# FTDI.net
KiCad netlist of a schematic drawn in Altium Designer
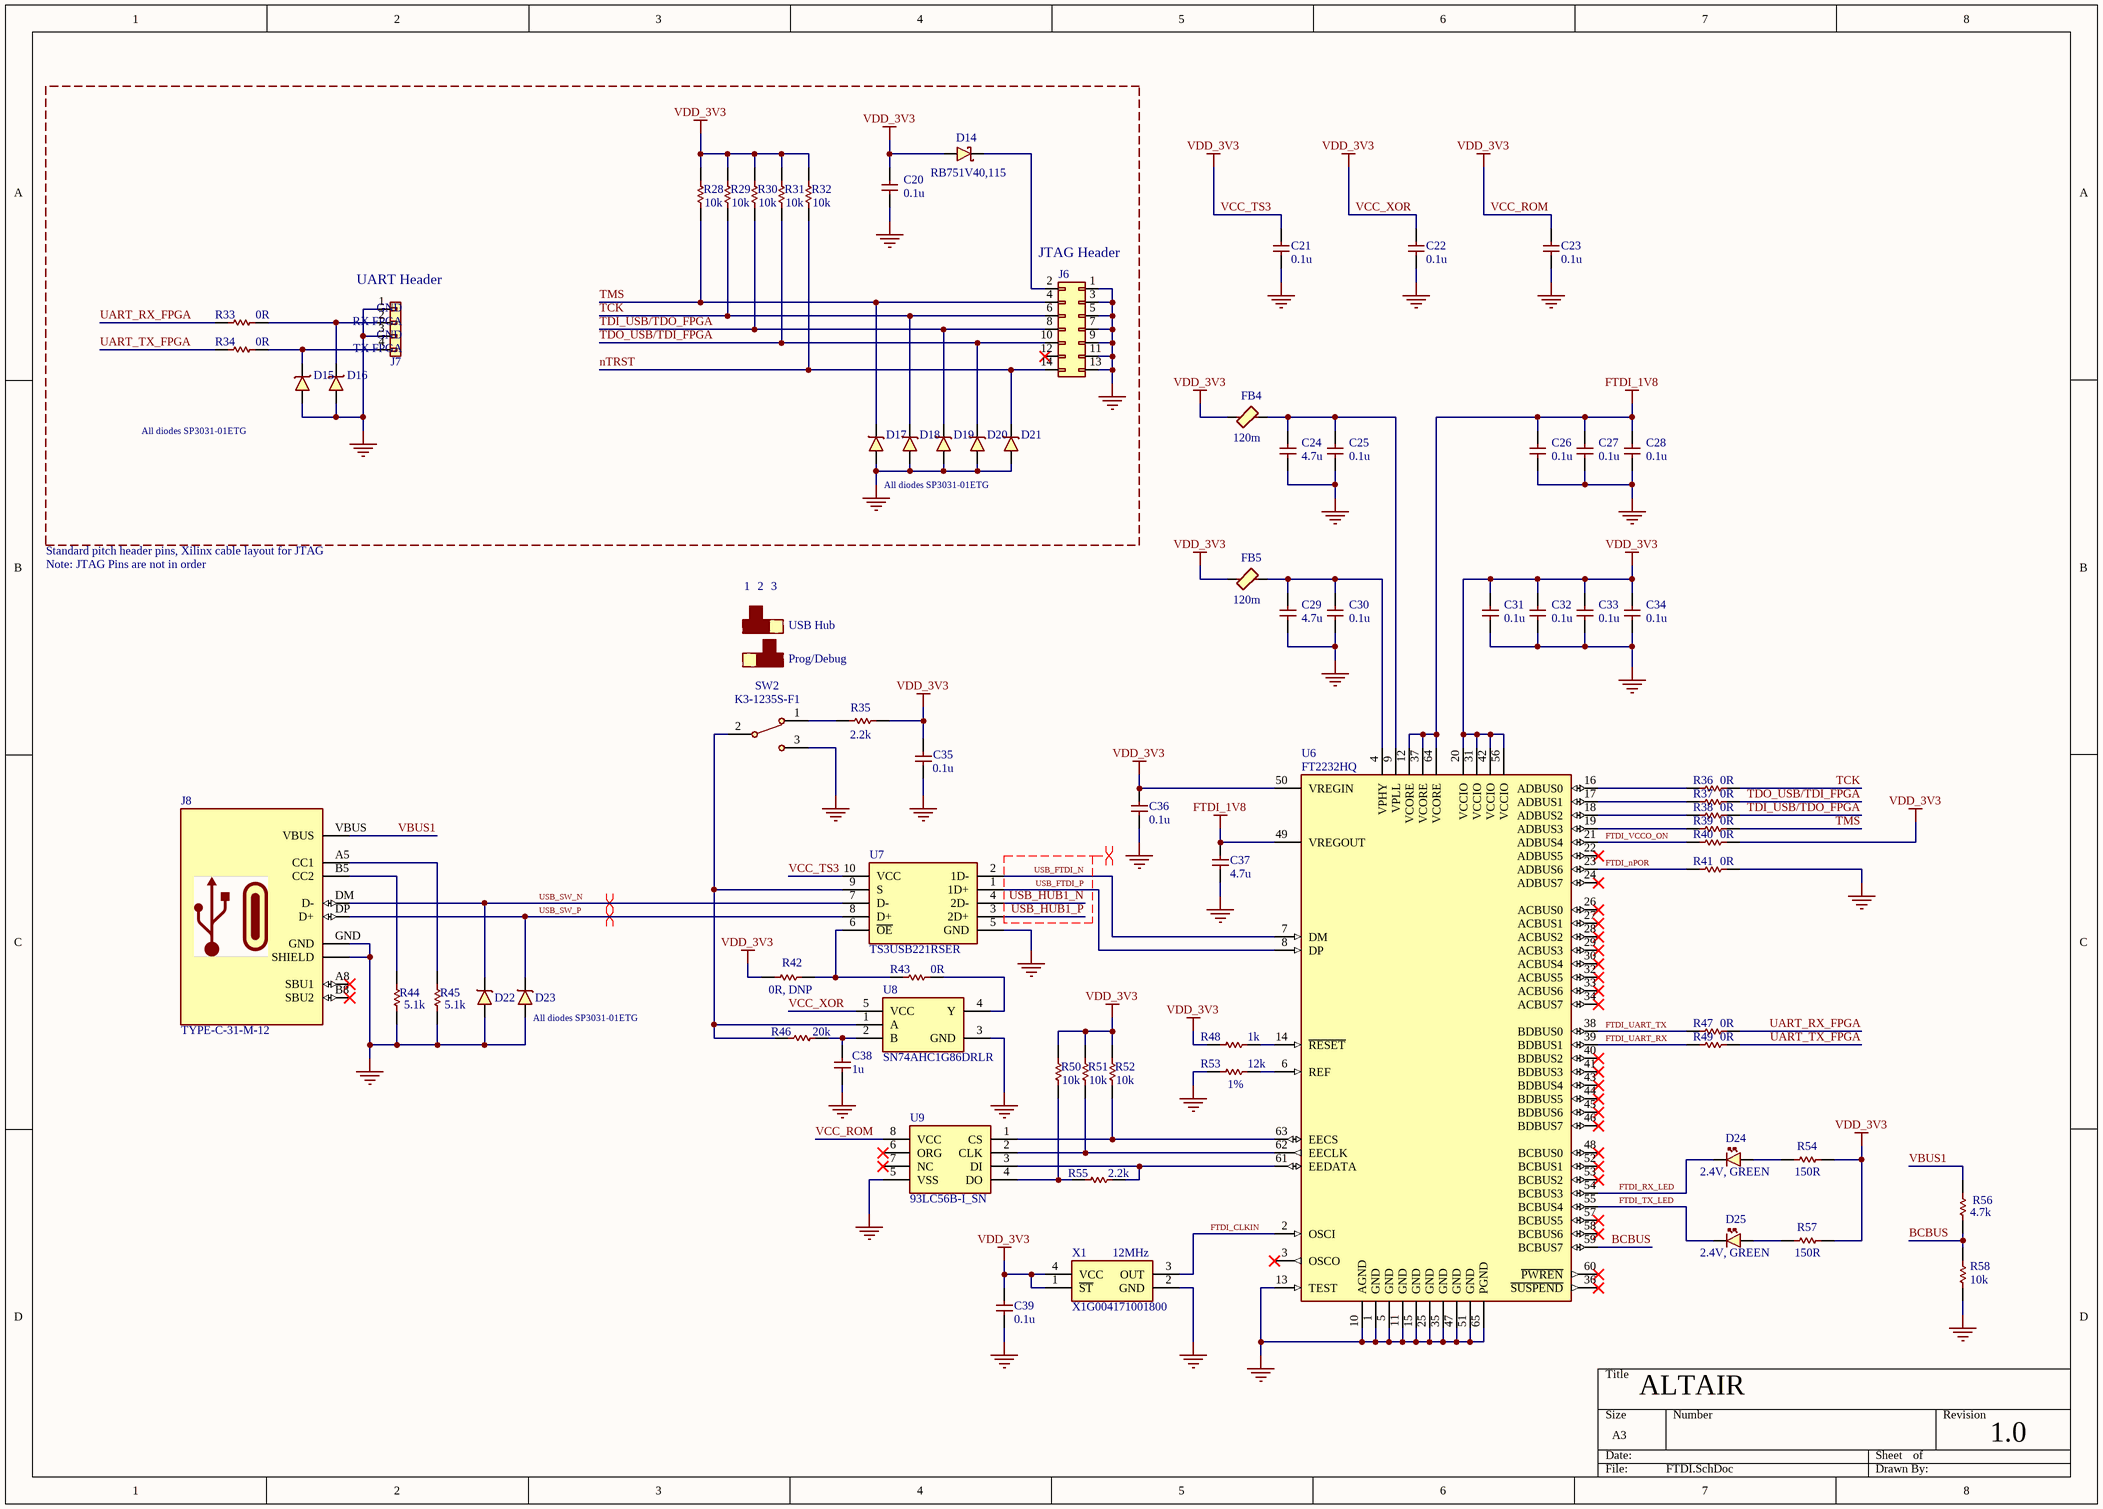
[diagram p0: FTDI.SchDoc]

(export (version "E")
  (design (tool "Eeschema 10.0.6"))
  (components
    (comp (ref "C20")
      (value "0.1u")
      (footprint "CAP_0402")
      (description "Capacitor SMD 0402")
      (fields (field (name "PART NO") "CL05B104KO5NNNC") (field (name "JLCPCB PART #") "C338112"))
      (libsource (lib "personalGenericLib") (part "CAP_0402"))
    )
    (comp (ref "C21")
      (value "0.1u")
      (footprint "CAP_0402")
      (description "Capacitor SMD 0402")
      (fields (field (name "PART NO") "CL05B104KO5NNNC") (field (name "JLCPCB PART #") "C338112"))
      (libsource (lib "personalGenericLib") (part "CAP_0402"))
    )
    (comp (ref "C22")
      (value "0.1u")
      (footprint "CAP_0402")
      (description "Capacitor SMD 0402")
      (fields (field (name "PART NO") "CL05B104KO5NNNC") (field (name "JLCPCB PART #") "C338112"))
      (libsource (lib "personalGenericLib") (part "CAP_0402"))
    )
    (comp (ref "C23")
      (value "0.1u")
      (footprint "CAP_0402")
      (description "Capacitor SMD 0402")
      (fields (field (name "PART NO") "CL05B104KO5NNNC") (field (name "JLCPCB PART #") "C338112"))
      (libsource (lib "personalGenericLib") (part "CAP_0402"))
    )
    (comp (ref "C24")
      (value "4.7u")
      (footprint "CAP_0402")
      (description "Capacitor SMD 0402")
      (fields (field (name "PART NO") "HGC0402R5475M250NTEJ") (field (name "JLCPCB PART #") "C22367824"))
      (libsource (lib "personalGenericLib") (part "CAP_0402"))
    )
    (comp (ref "C25")
      (value "0.1u")
      (footprint "CAP_0402")
      (description "Capacitor SMD 0402")
      (fields (field (name "PART NO") "CL05B104KO5NNNC") (field (name "JLCPCB PART #") "C338112"))
      (libsource (lib "personalGenericLib") (part "CAP_0402"))
    )
    (comp (ref "C26")
      (value "0.1u")
      (footprint "CAP_0402")
      (description "Capacitor SMD 0402")
      (fields (field (name "PART NO") "CL05B104KO5NNNC") (field (name "JLCPCB PART #") "C338112"))
      (libsource (lib "personalGenericLib") (part "CAP_0402"))
    )
    (comp (ref "C27")
      (value "0.1u")
      (footprint "CAP_0402")
      (description "Capacitor SMD 0402")
      (fields (field (name "PART NO") "CL05B104KO5NNNC") (field (name "JLCPCB PART #") "C338112"))
      (libsource (lib "personalGenericLib") (part "CAP_0402"))
    )
    (comp (ref "C28")
      (value "0.1u")
      (footprint "CAP_0402")
      (description "Capacitor SMD 0402")
      (fields (field (name "PART NO") "CL05B104KO5NNNC") (field (name "JLCPCB PART #") "C338112"))
      (libsource (lib "personalGenericLib") (part "CAP_0402"))
    )
    (comp (ref "C29")
      (value "4.7u")
      (footprint "CAP_0402")
      (description "Capacitor SMD 0402")
      (fields (field (name "PART NO") "HGC0402R5475M250NTEJ") (field (name "JLCPCB PART #") "C22367824"))
      (libsource (lib "personalGenericLib") (part "CAP_0402"))
    )
    (comp (ref "C30")
      (value "0.1u")
      (footprint "CAP_0402")
      (description "Capacitor SMD 0402")
      (fields (field (name "PART NO") "CL05B104KO5NNNC") (field (name "JLCPCB PART #") "C338112"))
      (libsource (lib "personalGenericLib") (part "CAP_0402"))
    )
    (comp (ref "C31")
      (value "0.1u")
      (footprint "CAP_0402")
      (description "Capacitor SMD 0402")
      (fields (field (name "PART NO") "CL05B104KO5NNNC") (field (name "JLCPCB PART #") "C338112"))
      (libsource (lib "personalGenericLib") (part "CAP_0402"))
    )
    (comp (ref "C32")
      (value "0.1u")
      (footprint "CAP_0402")
      (description "Capacitor SMD 0402")
      (fields (field (name "PART NO") "CL05B104KO5NNNC") (field (name "JLCPCB PART #") "C338112"))
      (libsource (lib "personalGenericLib") (part "CAP_0402"))
    )
    (comp (ref "C33")
      (value "0.1u")
      (footprint "CAP_0402")
      (description "Capacitor SMD 0402")
      (fields (field (name "PART NO") "CL05B104KO5NNNC") (field (name "JLCPCB PART #") "C338112"))
      (libsource (lib "personalGenericLib") (part "CAP_0402"))
    )
    (comp (ref "C34")
      (value "0.1u")
      (footprint "CAP_0402")
      (description "Capacitor SMD 0402")
      (fields (field (name "PART NO") "CL05B104KO5NNNC") (field (name "JLCPCB PART #") "C338112"))
      (libsource (lib "personalGenericLib") (part "CAP_0402"))
    )
    (comp (ref "C35")
      (value "0.1u")
      (footprint "CAP_0402")
      (description "Capacitor SMD 0402")
      (fields (field (name "PART NO") "CL05B104KO5NNNC") (field (name "JLCPCB PART #") "C338112"))
      (libsource (lib "personalGenericLib") (part "CAP_0402"))
    )
    (comp (ref "C36")
      (value "0.1u")
      (footprint "CAP_0402")
      (description "Capacitor SMD 0402")
      (fields (field (name "PART NO") "CL05B104KO5NNNC") (field (name "JLCPCB PART #") "C338112"))
      (libsource (lib "personalGenericLib") (part "CAP_0402"))
    )
    (comp (ref "C37")
      (value "4.7u")
      (footprint "CAP_0402")
      (description "Capacitor SMD 0402")
      (fields (field (name "PART NO") "HGC0402R5475M250NTEJ") (field (name "JLCPCB PART #") "C22367824"))
      (libsource (lib "personalGenericLib") (part "CAP_0402"))
    )
    (comp (ref "C38")
      (value "1u")
      (footprint "CAP_0402")
      (description "Capacitor SMD 0402")
      (fields (field (name "JLCPCB PART #") "C14445") (field (name "PART NO") "CL05A105KP5NNNC"))
      (libsource (lib "personalGenericLib") (part "CAP_0402"))
    )
    (comp (ref "C39")
      (value "0.1u")
      (footprint "CAP_0402")
      (description "Capacitor SMD 0402")
      (fields (field (name "PART NO") "CL05B104KO5NNNC") (field (name "JLCPCB PART #") "C338112"))
      (libsource (lib "personalGenericLib") (part "CAP_0402"))
    )
    (comp (ref "D14")
      (value "RB751V40,115")
      (footprint "SOD2512X110N")
      (description "Schottky Diode")
      (fields (field (name "JLCPCB PART #") "C553814"))
      (libsource (lib "personalGenericLib") (part "RB751V40,115"))
    )
    (comp (ref "D15")
      (value "SP3031-01ETG")
      (footprint "SP303101ETG")
      (description "TVS Diode (Uni-directional)")
      (fields (field (name "JLCPCB PART #") "C207283"))
      (libsource (lib "personalGenericLib") (part "SP3031-01ETG"))
    )
    (comp (ref "D16")
      (value "SP3031-01ETG")
      (footprint "SP303101ETG")
      (description "TVS Diode (Uni-directional)")
      (fields (field (name "JLCPCB PART #") "C207283"))
      (libsource (lib "personalGenericLib") (part "SP3031-01ETG"))
    )
    (comp (ref "D17")
      (value "SP3031-01ETG")
      (footprint "SP303101ETG")
      (description "TVS Diode (Uni-directional)")
      (fields (field (name "JLCPCB PART #") "C207283"))
      (libsource (lib "personalGenericLib") (part "SP3031-01ETG"))
    )
    (comp (ref "D18")
      (value "SP3031-01ETG")
      (footprint "SP303101ETG")
      (description "TVS Diode (Uni-directional)")
      (fields (field (name "JLCPCB PART #") "C207283"))
      (libsource (lib "personalGenericLib") (part "SP3031-01ETG"))
    )
    (comp (ref "D19")
      (value "SP3031-01ETG")
      (footprint "SP303101ETG")
      (description "TVS Diode (Uni-directional)")
      (fields (field (name "JLCPCB PART #") "C207283"))
      (libsource (lib "personalGenericLib") (part "SP3031-01ETG"))
    )
    (comp (ref "D20")
      (value "SP3031-01ETG")
      (footprint "SP303101ETG")
      (description "TVS Diode (Uni-directional)")
      (fields (field (name "JLCPCB PART #") "C207283"))
      (libsource (lib "personalGenericLib") (part "SP3031-01ETG"))
    )
    (comp (ref "D21")
      (value "SP3031-01ETG")
      (footprint "SP303101ETG")
      (description "TVS Diode (Uni-directional)")
      (fields (field (name "JLCPCB PART #") "C207283"))
      (libsource (lib "personalGenericLib") (part "SP3031-01ETG"))
    )
    (comp (ref "D22")
      (value "SP3031-01ETG")
      (footprint "SP303101ETG")
      (description "TVS Diode (Uni-directional)")
      (fields (field (name "JLCPCB PART #") "C207283"))
      (libsource (lib "personalGenericLib") (part "SP3031-01ETG"))
    )
    (comp (ref "D23")
      (value "SP3031-01ETG")
      (footprint "SP303101ETG")
      (description "TVS Diode (Uni-directional)")
      (fields (field (name "JLCPCB PART #") "C207283"))
      (libsource (lib "personalGenericLib") (part "SP3031-01ETG"))
    )
    (comp (ref "D24")
      (value "GREEN")
      (footprint "LED_0805_GREEN")
      (description "LED 0805 GREEN SMD")
      (fields
        (field (name "JLCPCB PART #") "C2986046")
        (field (name "NOTE/MISC") "2.4V, GREEN")
        (field (name "PART NO") "17-21SYGC/S530-E2/TR8")
      )
      (libsource (lib "personalGenericLib") (part "LED_0805_GREEN"))
    )
    (comp (ref "D25")
      (value "GREEN")
      (footprint "LED_0805_GREEN")
      (description "LED 0805 GREEN SMD")
      (fields
        (field (name "JLCPCB PART #") "C2986046")
        (field (name "NOTE/MISC") "2.4V, GREEN")
        (field (name "PART NO") "17-21SYGC/S530-E2/TR8")
      )
      (libsource (lib "personalGenericLib") (part "LED_0805_GREEN"))
    )
    (comp (ref "FB4")
      (value "120m")
      (footprint "FB_0201")
      (description "Ferrite Bead SMD 0201")
      (fields (field (name "PART NO") "MPZ0603S121HT000") (field (name "JLCPCB PART #") "C695597"))
      (libsource (lib "personalGenericLib") (part "FB_0201"))
    )
    (comp (ref "FB5")
      (value "120m")
      (footprint "FB_0201")
      (description "Ferrite Bead SMD 0201")
      (fields (field (name "PART NO") "MPZ0603S121HT000") (field (name "JLCPCB PART #") "C695597"))
      (libsource (lib "personalGenericLib") (part "FB_0201"))
    )
    (comp (ref "J6")
      (value "2x7Header")
      (footprint "67996114HLF")
      (description "Standard 2x7 pin 2.54mm pitch connector")
      (fields (field (name "JLCPCB PART #") "C706897") (field (name "PART NO") "X6521WV-2x07H-C60D30"))
      (libsource (lib "personalGenericLib") (part "2x7Header"))
    )
    (comp (ref "J7")
      (value "4xHeader")
      (footprint "HDRV4W95P0X254_1X4_1016X254X854P")
      (description "Standard 4 pin 2.54mm pitch connector")
      (fields (field (name "JLCPCB PART #") "C706876") (field (name "PART NO") "X6511WV-04H-C60D30"))
      (libsource (lib "personalGenericLib") (part "4xHeader"))
    )
    (comp (ref "J8")
      (value "TYPE-C-31-M-12")
      (footprint "HRO_TYPE-C-31-M-12")
      (description "USB2.0, Type C, Top mount, CH 1.68mm, Dual Row SMT")
      (fields (field (name "JLCPCB PART #") "C165948"))
      (libsource (lib "personalGenericLib") (part "TYPE-C-31-M-12"))
    )
    (comp (ref "R28")
      (value "10k")
      (footprint "RES_0402")
      (description "Resistor SMD 0402")
      (fields (field (name "JLCPCB PART #") "C60489") (field (name "PART NO") "RC0402JR-0710KL"))
      (libsource (lib "personalGenericLib") (part "RES_0402"))
    )
    (comp (ref "R29")
      (value "10k")
      (footprint "RES_0402")
      (description "Resistor SMD 0402")
      (fields (field (name "JLCPCB PART #") "C60489") (field (name "PART NO") "RC0402JR-0710KL"))
      (libsource (lib "personalGenericLib") (part "RES_0402"))
    )
    (comp (ref "R30")
      (value "10k")
      (footprint "RES_0402")
      (description "Resistor SMD 0402")
      (fields (field (name "JLCPCB PART #") "C60489") (field (name "PART NO") "RC0402JR-0710KL"))
      (libsource (lib "personalGenericLib") (part "RES_0402"))
    )
    (comp (ref "R31")
      (value "10k")
      (footprint "RES_0402")
      (description "Resistor SMD 0402")
      (fields (field (name "JLCPCB PART #") "C60489") (field (name "PART NO") "RC0402JR-0710KL"))
      (libsource (lib "personalGenericLib") (part "RES_0402"))
    )
    (comp (ref "R32")
      (value "10k")
      (footprint "RES_0402")
      (description "Resistor SMD 0402")
      (fields (field (name "JLCPCB PART #") "C60489") (field (name "PART NO") "RC0402JR-0710KL"))
      (libsource (lib "personalGenericLib") (part "RES_0402"))
    )
    (comp (ref "R33")
      (value "0R")
      (footprint "RES_0402")
      (description "Resistor SMD 0402")
      (fields (field (name "JLCPCB PART #") "C60485") (field (name "PART NO") "RC0402JR-070RL"))
      (libsource (lib "personalGenericLib") (part "RES_0402"))
    )
    (comp (ref "R34")
      (value "0R")
      (footprint "RES_0402")
      (description "Resistor SMD 0402")
      (fields (field (name "JLCPCB PART #") "C60485") (field (name "PART NO") "RC0402JR-070RL"))
      (libsource (lib "personalGenericLib") (part "RES_0402"))
    )
    (comp (ref "R35")
      (value "2.2k")
      (footprint "RES_0402")
      (description "Resistor SMD 0402")
      (fields (field (name "JLCPCB PART #") "C163447") (field (name "PART NO") "RC0402JR-072K2L"))
      (libsource (lib "personalGenericLib") (part "RES_0402"))
    )
    (comp (ref "R36")
      (value "0R")
      (footprint "RES_0402")
      (description "Resistor SMD 0402")
      (fields (field (name "JLCPCB PART #") "C60485") (field (name "PART NO") "RC0402JR-070RL"))
      (libsource (lib "personalGenericLib") (part "RES_0402"))
    )
    (comp (ref "R37")
      (value "0R")
      (footprint "RES_0402")
      (description "Resistor SMD 0402")
      (fields (field (name "JLCPCB PART #") "C60485") (field (name "PART NO") "RC0402JR-070RL"))
      (libsource (lib "personalGenericLib") (part "RES_0402"))
    )
    (comp (ref "R38")
      (value "0R")
      (footprint "RES_0402")
      (description "Resistor SMD 0402")
      (fields (field (name "JLCPCB PART #") "C60485") (field (name "PART NO") "RC0402JR-070RL"))
      (libsource (lib "personalGenericLib") (part "RES_0402"))
    )
    (comp (ref "R39")
      (value "0R")
      (footprint "RES_0402")
      (description "Resistor SMD 0402")
      (fields (field (name "JLCPCB PART #") "C60485") (field (name "PART NO") "RC0402JR-070RL"))
      (libsource (lib "personalGenericLib") (part "RES_0402"))
    )
    (comp (ref "R40")
      (value "0R")
      (footprint "RES_0402")
      (description "Resistor SMD 0402")
      (fields (field (name "JLCPCB PART #") "C60485") (field (name "PART NO") "RC0402JR-070RL"))
      (libsource (lib "personalGenericLib") (part "RES_0402"))
    )
    (comp (ref "R41")
      (value "0R")
      (footprint "RES_0402")
      (description "Resistor SMD 0402")
      (fields (field (name "JLCPCB PART #") "C60485") (field (name "PART NO") "RC0402JR-070RL"))
      (libsource (lib "personalGenericLib") (part "RES_0402"))
    )
    (comp (ref "R42")
      (value "0R, DNP")
      (footprint "RES_0402")
      (description "Resistor SMD 0402")
      (fields (field (name "JLCPCB PART #") "C60485") (field (name "PART NO") "RC0402JR-070RL"))
      (libsource (lib "personalGenericLib") (part "RES_0402"))
    )
    (comp (ref "R43")
      (value "0R")
      (footprint "RES_0402")
      (description "Resistor SMD 0402")
      (fields (field (name "JLCPCB PART #") "C60485") (field (name "PART NO") "RC0402JR-070RL"))
      (libsource (lib "personalGenericLib") (part "RES_0402"))
    )
    (comp (ref "R44")
      (value "5.1k")
      (footprint "RES_0402")
      (description "Resistor SMD 0402")
      (fields (field (name "JLCPCB PART #") "C105873") (field (name "PART NO") "RC0402JR-075K1L"))
      (libsource (lib "personalGenericLib") (part "RES_0402"))
    )
    (comp (ref "R45")
      (value "5.1k")
      (footprint "RES_0402")
      (description "Resistor SMD 0402")
      (fields (field (name "JLCPCB PART #") "C105873") (field (name "PART NO") "RC0402JR-075K1L"))
      (libsource (lib "personalGenericLib") (part "RES_0402"))
    )
    (comp (ref "R46")
      (value "20k")
      (footprint "RES_0402")
      (description "Resistor SMD 0402")
      (fields (field (name "JLCPCB PART #") "C93942") (field (name "PART NO") "RC0402FR-0720KL"))
      (libsource (lib "personalGenericLib") (part "RES_0402"))
    )
    (comp (ref "R47")
      (value "0R")
      (footprint "RES_0402")
      (description "Resistor SMD 0402")
      (fields (field (name "JLCPCB PART #") "C60485") (field (name "PART NO") "RC0402JR-070RL"))
      (libsource (lib "personalGenericLib") (part "RES_0402"))
    )
    (comp (ref "R48")
      (value "1k")
      (footprint "RES_0402")
      (description "Resistor SMD 0402")
      (fields (field (name "JLCPCB PART #") "C105637") (field (name "PART NO") "RC0402JR-071KL"))
      (libsource (lib "personalGenericLib") (part "RES_0402"))
    )
    (comp (ref "R49")
      (value "0R")
      (footprint "RES_0402")
      (description "Resistor SMD 0402")
      (fields (field (name "JLCPCB PART #") "C60485") (field (name "PART NO") "RC0402JR-070RL"))
      (libsource (lib "personalGenericLib") (part "RES_0402"))
    )
    (comp (ref "R50")
      (value "10k")
      (footprint "RES_0402")
      (description "Resistor SMD 0402")
      (fields (field (name "JLCPCB PART #") "C60489") (field (name "PART NO") "RC0402JR-0710KL"))
      (libsource (lib "personalGenericLib") (part "RES_0402"))
    )
    (comp (ref "R51")
      (value "10k")
      (footprint "RES_0402")
      (description "Resistor SMD 0402")
      (fields (field (name "JLCPCB PART #") "C60489") (field (name "PART NO") "RC0402JR-0710KL"))
      (libsource (lib "personalGenericLib") (part "RES_0402"))
    )
    (comp (ref "R52")
      (value "10k")
      (footprint "RES_0402")
      (description "Resistor SMD 0402")
      (fields (field (name "JLCPCB PART #") "C60489") (field (name "PART NO") "RC0402JR-0710KL"))
      (libsource (lib "personalGenericLib") (part "RES_0402"))
    )
    (comp (ref "R53")
      (value "12k")
      (footprint "RES_0402")
      (description "Resistor SMD 0402")
      (fields
        (field (name "JLCPCB PART #") "C114760")
        (field (name "NOTE/MISC") "1%")
        (field (name "PART NO") "RC0402FR-0712KL")
      )
      (libsource (lib "personalGenericLib") (part "RES_0402"))
    )
    (comp (ref "R54")
      (value "150R")
      (footprint "RES_0402")
      (description "Resistor SMD 0402")
      (fields (field (name "JLCPCB PART #") "C138054") (field (name "PART NO") "RC0402FR-07150RL"))
      (libsource (lib "personalGenericLib") (part "RES_0402"))
    )
    (comp (ref "R55")
      (value "2.2k")
      (footprint "RES_0402")
      (description "Resistor SMD 0402")
      (fields (field (name "PART NO") "RC0402JR-072K2L") (field (name "JLCPCB PART #") "C163447"))
      (libsource (lib "personalGenericLib") (part "RES_0402"))
    )
    (comp (ref "R56")
      (value "4.7k")
      (footprint "RES_0402")
      (description "Resistor SMD 0402")
      (fields (field (name "JLCPCB PART #") "C105870") (field (name "PART NO") "RC0402JR-074K7L"))
      (libsource (lib "personalGenericLib") (part "RES_0402"))
    )
    (comp (ref "R57")
      (value "150R")
      (footprint "RES_0402")
      (description "Resistor SMD 0402")
      (fields (field (name "JLCPCB PART #") "C138054") (field (name "PART NO") "RC0402FR-07150RL"))
      (libsource (lib "personalGenericLib") (part "RES_0402"))
    )
    (comp (ref "R58")
      (value "10k")
      (footprint "RES_0402")
      (description "Resistor SMD 0402")
      (fields (field (name "JLCPCB PART #") "C60489") (field (name "PART NO") "RC0402JR-0710KL"))
      (libsource (lib "personalGenericLib") (part "RES_0402"))
    )
    (comp (ref "SW2")
      (value "K3-1235S-F1")
      (footprint "K3-1235S-F1")
      (description "Slide Switch SMD")
      (fields (field (name "JLCPCB PART #") "C92660"))
      (libsource (lib "personalGenericLib") (part "K3-1235S-F1"))
    )
    (comp (ref "U6")
      (value "FT2232HQ")
      (footprint "FP-FT2232HQ-Reel-IPC_C")
      (description "Dual High Speed USB To Multipurpose UART/FIFO IC, 64-pin LQFP, Tape and Reel")
      (fields (field (name "JLCPCB PART #") "C193662"))
      (libsource (lib "personalGenericLib") (part "FT2232HQ-Reel"))
    )
    (comp (ref "U7")
      (value "TS3USB221RSER")
      (footprint "RSE(R-PUQFN-N10)")
      (description "Diff Pair MUX/DEMUX")
      (fields (field (name "JLCPCB PART #") "C130085"))
      (libsource (lib "personalGenericLib") (part "TS3USB221RSER"))
    )
    (comp (ref "U8")
      (value "SN74AHC1G86DRLR")
      (footprint "SOTFL50P160X60-5N")
      (description "XOR Gate, 2 inputs 1 output")
      (fields (field (name "JLCPCB PART #") "C2682053"))
      (libsource (lib "personalGenericLib") (part "SN74AHC1G86DRLR"))
    )
    (comp (ref "U9")
      (value "93LC56B-I_SN")
      (footprint "SOIC127P600X175-8N")
      (description "Integrated Circuit")
      (fields (field (name "JLCPCB PART #") "C183620"))
      (libsource (lib "personalGenericLib") (part "93LC56B-I_SN"))
    )
    (comp (ref "X1")
      (value "X1G004171001800")
      (footprint "XTAL_2520")
      (description "Programmable Oscillator 12MHz")
      (fields
        (field (name "JLCPCB PART #") "C255991")
        (field (name "NOTE/MISC") "12MHz")
        (field (name "PART NO") "X1G0041710018")
      )
      (libsource (lib "personalGenericLib") (part "X1G004171001800"))
    )
  )
  (nets
    (net (code "1") (name "/BCBUS") (class "Default")
      (node (ref "R56") (pin "2") (pinfunction "2_2") (pintype "passive"))
      (node (ref "R58") (pin "1") (pinfunction "1_1") (pintype "passive"))
      (node (ref "U6") (pin "59") (pinfunction "BCBUS7_59") (pintype "bidirectional"))
    )
    (net (code "2") (name "/FTDI_CLKIN") (class "Default")
      (node (ref "U6") (pin "2") (pinfunction "OSCI_2") (pintype "input"))
      (node (ref "X1") (pin "3") (pinfunction "OUT_3") (pintype "passive"))
    )
    (net (code "3") (name "/FTDI_RX_LED") (class "Default")
      (node (ref "D24") (pin "K") (pinfunction "K_K") (pintype "passive"))
      (node (ref "U6") (pin "54") (pinfunction "BCBUS3_54") (pintype "bidirectional"))
    )
    (net (code "4") (name "/FTDI_TX_LED") (class "Default")
      (node (ref "D25") (pin "K") (pinfunction "K_K") (pintype "passive"))
      (node (ref "U6") (pin "55") (pinfunction "BCBUS4_55") (pintype "bidirectional"))
    )
    (net (code "5") (name "/FTDI_UART_RX") (class "Default")
      (node (ref "R49") (pin "1") (pinfunction "1_1") (pintype "passive"))
      (node (ref "U6") (pin "39") (pinfunction "BDBUS1_39") (pintype "bidirectional"))
    )
    (net (code "6") (name "/FTDI_UART_TX") (class "Default")
      (node (ref "R47") (pin "1") (pinfunction "1_1") (pintype "passive"))
      (node (ref "U6") (pin "38") (pinfunction "BDBUS0_38") (pintype "bidirectional"))
    )
    (net (code "7") (name "/FTDI_VCCO_ON") (class "Default")
      (node (ref "R40") (pin "1") (pinfunction "1_1") (pintype "passive"))
      (node (ref "U6") (pin "21") (pinfunction "ADBUS4_21") (pintype "bidirectional"))
    )
    (net (code "8") (name "/FTDI_nPOR") (class "Default")
      (node (ref "R41") (pin "1") (pinfunction "1_1") (pintype "passive"))
      (node (ref "U6") (pin "23") (pinfunction "ADBUS6_23") (pintype "bidirectional"))
    )
    (net (code "9") (name "/TCK") (class "Default")
      (node (ref "D18") (pin "1") (pinfunction "K_1") (pintype "passive"))
      (node (ref "J6") (pin "6") (pinfunction "6_6") (pintype "passive"))
      (node (ref "R29") (pin "2") (pinfunction "2_2") (pintype "passive"))
      (node (ref "R36") (pin "2") (pinfunction "2_2") (pintype "passive"))
    )
    (net (code "10") (name "/TDI_USB{slash}TDO_FPGA") (class "Default")
      (node (ref "D19") (pin "1") (pinfunction "K_1") (pintype "passive"))
      (node (ref "J6") (pin "8") (pinfunction "8_8") (pintype "passive"))
      (node (ref "R30") (pin "2") (pinfunction "2_2") (pintype "passive"))
      (node (ref "R38") (pin "2") (pinfunction "2_2") (pintype "passive"))
    )
    (net (code "11") (name "/TDO_USB{slash}TDI_FPGA") (class "Default")
      (node (ref "D20") (pin "1") (pinfunction "K_1") (pintype "passive"))
      (node (ref "J6") (pin "10") (pinfunction "10_10") (pintype "passive"))
      (node (ref "R31") (pin "2") (pinfunction "2_2") (pintype "passive"))
      (node (ref "R37") (pin "2") (pinfunction "2_2") (pintype "passive"))
    )
    (net (code "12") (name "/TMS") (class "Default")
      (node (ref "D17") (pin "1") (pinfunction "K_1") (pintype "passive"))
      (node (ref "J6") (pin "4") (pinfunction "4_4") (pintype "passive"))
      (node (ref "R28") (pin "2") (pinfunction "2_2") (pintype "passive"))
      (node (ref "R39") (pin "2") (pinfunction "2_2") (pintype "passive"))
    )
    (net (code "13") (name "/UART_RX_FPGA") (class "Default")
      (node (ref "R33") (pin "1") (pinfunction "1_1") (pintype "passive"))
      (node (ref "R47") (pin "2") (pinfunction "2_2") (pintype "passive"))
    )
    (net (code "14") (name "/UART_TX_FPGA") (class "Default")
      (node (ref "R34") (pin "1") (pinfunction "1_1") (pintype "passive"))
      (node (ref "R49") (pin "2") (pinfunction "2_2") (pintype "passive"))
    )
    (net (code "15") (name "/USB_FTDI_N") (class "Default")
      (node (ref "U6") (pin "7") (pinfunction "DM_7") (pintype "input"))
      (node (ref "U7") (pin "2") (pinfunction "1D-_2") (pintype "passive"))
    )
    (net (code "16") (name "/USB_FTDI_P") (class "Default")
      (node (ref "U6") (pin "8") (pinfunction "DP_8") (pintype "input"))
      (node (ref "U7") (pin "1") (pinfunction "1D+_1") (pintype "passive"))
    )
    (net (code "17") (name "/USB_HUB1_N") (class "Default")
      (node (ref "U7") (pin "4") (pinfunction "2D-_4") (pintype "passive"))
    )
    (net (code "18") (name "/USB_HUB1_P") (class "Default")
      (node (ref "U7") (pin "3") (pinfunction "2D+_3") (pintype "passive"))
    )
    (net (code "19") (name "/USB_SW_N") (class "Default")
      (node (ref "D22") (pin "1") (pinfunction "K_1") (pintype "passive"))
      (node (ref "J8") (pin "DM") (pinfunction "D-_DM") (pintype "bidirectional"))
      (node (ref "U7") (pin "7") (pinfunction "D-_7") (pintype "passive"))
    )
    (net (code "20") (name "/USB_SW_P") (class "Default")
      (node (ref "D23") (pin "1") (pinfunction "K_1") (pintype "passive"))
      (node (ref "J8") (pin "DP") (pinfunction "D+_DP") (pintype "bidirectional"))
      (node (ref "U7") (pin "8") (pinfunction "D+_8") (pintype "passive"))
    )
    (net (code "21") (name "/VBUS1") (class "Default")
      (node (ref "J8") (pin "VBUS") (pinfunction "VBUS_VBUS") (pintype "passive"))
      (node (ref "R56") (pin "1") (pinfunction "1_1") (pintype "passive"))
    )
    (net (code "22") (name "/nTRST") (class "Default")
      (node (ref "D21") (pin "1") (pinfunction "K_1") (pintype "passive"))
      (node (ref "J6") (pin "14") (pinfunction "14_14") (pintype "passive"))
      (node (ref "R32") (pin "2") (pinfunction "2_2") (pintype "passive"))
    )
    (net (code "23") (name "FTDI_1V8") (class "Default")
      (node (ref "C26") (pin "2") (pinfunction "2_2") (pintype "passive"))
      (node (ref "C27") (pin "2") (pinfunction "2_2") (pintype "passive"))
      (node (ref "C28") (pin "2") (pinfunction "2_2") (pintype "passive"))
      (node (ref "C37") (pin "2") (pinfunction "2_2") (pintype "passive"))
      (node (ref "U6") (pin "12") (pinfunction "VCORE_12") (pintype "power_in"))
      (node (ref "U6") (pin "37") (pinfunction "VCORE_37") (pintype "power_in"))
      (node (ref "U6") (pin "49") (pinfunction "VREGOUT_49") (pintype "power_in"))
      (node (ref "U6") (pin "64") (pinfunction "VCORE_64") (pintype "power_in"))
    )
    (net (code "24") (name "GND") (class "Default")
      (node (ref "C20") (pin "1") (pinfunction "1_1") (pintype "passive"))
      (node (ref "C21") (pin "1") (pinfunction "1_1") (pintype "passive"))
      (node (ref "C22") (pin "1") (pinfunction "1_1") (pintype "passive"))
      (node (ref "C23") (pin "1") (pinfunction "1_1") (pintype "passive"))
      (node (ref "C24") (pin "1") (pinfunction "1_1") (pintype "passive"))
      (node (ref "C25") (pin "1") (pinfunction "1_1") (pintype "passive"))
      (node (ref "C26") (pin "1") (pinfunction "1_1") (pintype "passive"))
      (node (ref "C27") (pin "1") (pinfunction "1_1") (pintype "passive"))
      (node (ref "C28") (pin "1") (pinfunction "1_1") (pintype "passive"))
      (node (ref "C29") (pin "1") (pinfunction "1_1") (pintype "passive"))
      (node (ref "C30") (pin "1") (pinfunction "1_1") (pintype "passive"))
      (node (ref "C31") (pin "1") (pinfunction "1_1") (pintype "passive"))
      (node (ref "C32") (pin "1") (pinfunction "1_1") (pintype "passive"))
      (node (ref "C33") (pin "1") (pinfunction "1_1") (pintype "passive"))
      (node (ref "C34") (pin "1") (pinfunction "1_1") (pintype "passive"))
      (node (ref "C35") (pin "1") (pinfunction "1_1") (pintype "passive"))
      (node (ref "C36") (pin "1") (pinfunction "1_1") (pintype "passive"))
      (node (ref "C37") (pin "1") (pinfunction "1_1") (pintype "passive"))
      (node (ref "C38") (pin "1") (pinfunction "1_1") (pintype "passive"))
      (node (ref "C39") (pin "1") (pinfunction "1_1") (pintype "passive"))
      (node (ref "D15") (pin "2") (pinfunction "A_2") (pintype "passive"))
      (node (ref "D16") (pin "2") (pinfunction "A_2") (pintype "passive"))
      (node (ref "D17") (pin "2") (pinfunction "A_2") (pintype "passive"))
      (node (ref "D18") (pin "2") (pinfunction "A_2") (pintype "passive"))
      (node (ref "D19") (pin "2") (pinfunction "A_2") (pintype "passive"))
      (node (ref "D20") (pin "2") (pinfunction "A_2") (pintype "passive"))
      (node (ref "D21") (pin "2") (pinfunction "A_2") (pintype "passive"))
      (node (ref "D22") (pin "2") (pinfunction "A_2") (pintype "passive"))
      (node (ref "D23") (pin "2") (pinfunction "A_2") (pintype "passive"))
      (node (ref "J6") (pin "1") (pinfunction "1_1") (pintype "passive"))
      (node (ref "J6") (pin "11") (pinfunction "11_11") (pintype "passive"))
      (node (ref "J6") (pin "13") (pinfunction "13_13") (pintype "passive"))
      (node (ref "J6") (pin "3") (pinfunction "3_3") (pintype "passive"))
      (node (ref "J6") (pin "5") (pinfunction "5_5") (pintype "passive"))
      (node (ref "J6") (pin "7") (pinfunction "7_7") (pintype "passive"))
      (node (ref "J6") (pin "9") (pinfunction "9_9") (pintype "passive"))
      (node (ref "J7") (pin "1") (pinfunction "1_1") (pintype "passive"))
      (node (ref "J7") (pin "3") (pinfunction "3_3") (pintype "passive"))
      (node (ref "J8") (pin "GND") (pinfunction "GND_GND") (pintype "passive"))
      (node (ref "J8") (pin "SHLD") (pinfunction "SHIELD_SHLD") (pintype "passive"))
      (node (ref "R41") (pin "2") (pinfunction "2_2") (pintype "passive"))
      (node (ref "R44") (pin "2") (pinfunction "2_2") (pintype "passive"))
      (node (ref "R45") (pin "2") (pinfunction "2_2") (pintype "passive"))
      (node (ref "R53") (pin "1") (pinfunction "1_1") (pintype "passive"))
      (node (ref "R58") (pin "2") (pinfunction "2_2") (pintype "passive"))
      (node (ref "SW2") (pin "3") (pinfunction "3_3") (pintype "passive"))
      (node (ref "U6") (pin "1") (pinfunction "GND_1") (pintype "power_in"))
      (node (ref "U6") (pin "10") (pinfunction "AGND_10") (pintype "power_in"))
      (node (ref "U6") (pin "11") (pinfunction "GND_11") (pintype "power_in"))
      (node (ref "U6") (pin "13") (pinfunction "TEST_13") (pintype "input"))
      (node (ref "U6") (pin "15") (pinfunction "GND_15") (pintype "power_in"))
      (node (ref "U6") (pin "25") (pinfunction "GND_25") (pintype "power_in"))
      (node (ref "U6") (pin "35") (pinfunction "GND_35") (pintype "power_in"))
      (node (ref "U6") (pin "47") (pinfunction "GND_47") (pintype "power_in"))
      (node (ref "U6") (pin "5") (pinfunction "GND_5") (pintype "power_in"))
      (node (ref "U6") (pin "51") (pinfunction "GND_51") (pintype "power_in"))
      (node (ref "U6") (pin "65") (pinfunction "PGND_65") (pintype "power_in"))
      (node (ref "U7") (pin "5") (pinfunction "GND_5") (pintype "passive"))
      (node (ref "U8") (pin "3") (pinfunction "GND_3") (pintype "passive"))
      (node (ref "U9") (pin "5") (pinfunction "VSS_5") (pintype "passive"))
      (node (ref "X1") (pin "2") (pinfunction "GND_2") (pintype "passive"))
    )
    (net (code "25") (name "Net-(D14-Pad1)") (class "Default")
      (node (ref "D14") (pin "1") (pinfunction "1_1") (pintype "passive"))
      (node (ref "J6") (pin "2") (pinfunction "2_2") (pintype "passive"))
    )
    (net (code "26") (name "Net-(D15-K)") (class "Default")
      (node (ref "D15") (pin "1") (pinfunction "K_1") (pintype "passive"))
      (node (ref "J7") (pin "4") (pinfunction "4_4") (pintype "passive"))
      (node (ref "R34") (pin "2") (pinfunction "2_2") (pintype "passive"))
    )
    (net (code "27") (name "Net-(D16-K)") (class "Default")
      (node (ref "D16") (pin "1") (pinfunction "K_1") (pintype "passive"))
      (node (ref "J7") (pin "2") (pinfunction "2_2") (pintype "passive"))
      (node (ref "R33") (pin "2") (pinfunction "2_2") (pintype "passive"))
    )
    (net (code "28") (name "Net-(D24-PadA)") (class "Default")
      (node (ref "D24") (pin "A") (pinfunction "A_A") (pintype "passive"))
      (node (ref "R54") (pin "1") (pinfunction "1_1") (pintype "passive"))
    )
    (net (code "29") (name "Net-(D25-PadA)") (class "Default")
      (node (ref "D25") (pin "A") (pinfunction "A_A") (pintype "passive"))
      (node (ref "R57") (pin "1") (pinfunction "1_1") (pintype "passive"))
    )
    (net (code "30") (name "Net-(J8-CC1)") (class "Default")
      (node (ref "J8") (pin "A5") (pinfunction "CC1_A5") (pintype "passive"))
      (node (ref "R45") (pin "1") (pinfunction "1_1") (pintype "passive"))
    )
    (net (code "31") (name "Net-(J8-CC2)") (class "Default")
      (node (ref "J8") (pin "B5") (pinfunction "CC2_B5") (pintype "passive"))
      (node (ref "R44") (pin "1") (pinfunction "1_1") (pintype "passive"))
    )
    (net (code "32") (name "Net-(R35-Pad1)") (class "Default")
      (node (ref "R35") (pin "1") (pinfunction "1_1") (pintype "passive"))
      (node (ref "SW2") (pin "1") (pinfunction "1_1") (pintype "passive"))
    )
    (net (code "33") (name "Net-(SW2-C)") (class "Default")
      (node (ref "R46") (pin "1") (pinfunction "1_1") (pintype "passive"))
      (node (ref "SW2") (pin "2") (pinfunction "C_2") (pintype "passive"))
      (node (ref "U7") (pin "9") (pinfunction "S_9") (pintype "passive"))
      (node (ref "U8") (pin "1") (pinfunction "A_1") (pintype "passive"))
    )
    (net (code "34") (name "Net-(U6-ADBUS0)") (class "Default")
      (node (ref "R36") (pin "1") (pinfunction "1_1") (pintype "passive"))
      (node (ref "U6") (pin "16") (pinfunction "ADBUS0_16") (pintype "bidirectional"))
    )
    (net (code "35") (name "Net-(U6-ADBUS1)") (class "Default")
      (node (ref "R37") (pin "1") (pinfunction "1_1") (pintype "passive"))
      (node (ref "U6") (pin "17") (pinfunction "ADBUS1_17") (pintype "bidirectional"))
    )
    (net (code "36") (name "Net-(U6-ADBUS2)") (class "Default")
      (node (ref "R38") (pin "1") (pinfunction "1_1") (pintype "passive"))
      (node (ref "U6") (pin "18") (pinfunction "ADBUS2_18") (pintype "bidirectional"))
    )
    (net (code "37") (name "Net-(U6-ADBUS3)") (class "Default")
      (node (ref "R39") (pin "1") (pinfunction "1_1") (pintype "passive"))
      (node (ref "U6") (pin "19") (pinfunction "ADBUS3_19") (pintype "bidirectional"))
    )
    (net (code "38") (name "Net-(U6-EECLK)") (class "Default")
      (node (ref "R51") (pin "2") (pinfunction "2_2") (pintype "passive"))
      (node (ref "U6") (pin "62") (pinfunction "EECLK_62") (pintype "output"))
      (node (ref "U9") (pin "2") (pinfunction "CLK_2") (pintype "passive"))
    )
    (net (code "39") (name "Net-(U6-EECS)") (class "Default")
      (node (ref "R52") (pin "2") (pinfunction "2_2") (pintype "passive"))
      (node (ref "U6") (pin "63") (pinfunction "EECS_63") (pintype "bidirectional"))
      (node (ref "U9") (pin "1") (pinfunction "CS_1") (pintype "passive"))
    )
    (net (code "40") (name "Net-(U6-EEDATA)") (class "Default")
      (node (ref "R55") (pin "1") (pinfunction "1_1") (pintype "passive"))
      (node (ref "U6") (pin "61") (pinfunction "EEDATA_61") (pintype "bidirectional"))
      (node (ref "U9") (pin "3") (pinfunction "DI_3") (pintype "passive"))
    )
    (net (code "41") (name "Net-(U6-REF)") (class "Default")
      (node (ref "R53") (pin "2") (pinfunction "2_2") (pintype "passive"))
      (node (ref "U6") (pin "6") (pinfunction "REF_6") (pintype "input"))
    )
    (net (code "42") (name "Net-(U6-VPHY)") (class "Default")
      (node (ref "C29") (pin "2") (pinfunction "2_2") (pintype "passive"))
      (node (ref "C30") (pin "2") (pinfunction "2_2") (pintype "passive"))
      (node (ref "FB5") (pin "2") (pinfunction "2_2") (pintype "passive"))
      (node (ref "U6") (pin "4") (pinfunction "VPHY_4") (pintype "power_in"))
    )
    (net (code "43") (name "Net-(U6-VPLL)") (class "Default")
      (node (ref "C24") (pin "2") (pinfunction "2_2") (pintype "passive"))
      (node (ref "C25") (pin "2") (pinfunction "2_2") (pintype "passive"))
      (node (ref "FB4") (pin "2") (pinfunction "2_2") (pintype "passive"))
      (node (ref "U6") (pin "9") (pinfunction "VPLL_9") (pintype "power_in"))
    )
    (net (code "44") (name "Net-(U6-~{RESET})") (class "Default")
      (node (ref "R48") (pin "2") (pinfunction "2_2") (pintype "passive"))
      (node (ref "U6") (pin "14") (pinfunction "~{RESET}_14") (pintype "input"))
    )
    (net (code "45") (name "Net-(U7-~{OE})") (class "Default")
      (node (ref "R42") (pin "2") (pinfunction "2_2") (pintype "passive"))
      (node (ref "R43") (pin "1") (pinfunction "1_1") (pintype "passive"))
      (node (ref "U7") (pin "6") (pinfunction "~{OE}_6") (pintype "passive"))
    )
    (net (code "46") (name "Net-(U8-B)") (class "Default")
      (node (ref "C38") (pin "2") (pinfunction "2_2") (pintype "passive"))
      (node (ref "R46") (pin "2") (pinfunction "2_2") (pintype "passive"))
      (node (ref "U8") (pin "2") (pinfunction "B_2") (pintype "passive"))
    )
    (net (code "47") (name "Net-(U8-Y)") (class "Default")
      (node (ref "R43") (pin "2") (pinfunction "2_2") (pintype "passive"))
      (node (ref "U8") (pin "4") (pinfunction "Y_4") (pintype "passive"))
    )
    (net (code "48") (name "Net-(U9-DO)") (class "Default")
      (node (ref "R50") (pin "2") (pinfunction "2_2") (pintype "passive"))
      (node (ref "R55") (pin "2") (pinfunction "2_2") (pintype "passive"))
      (node (ref "U9") (pin "4") (pinfunction "DO_4") (pintype "passive"))
    )
    (net (code "49") (name "VDD_3V3") (class "Default")
      (node (ref "C20") (pin "2") (pinfunction "2_2") (pintype "passive"))
      (node (ref "C21") (pin "2") (pinfunction "2_2") (pintype "passive"))
      (node (ref "C22") (pin "2") (pinfunction "2_2") (pintype "passive"))
      (node (ref "C23") (pin "2") (pinfunction "2_2") (pintype "passive"))
      (node (ref "C31") (pin "2") (pinfunction "2_2") (pintype "passive"))
      (node (ref "C32") (pin "2") (pinfunction "2_2") (pintype "passive"))
      (node (ref "C33") (pin "2") (pinfunction "2_2") (pintype "passive"))
      (node (ref "C34") (pin "2") (pinfunction "2_2") (pintype "passive"))
      (node (ref "C35") (pin "2") (pinfunction "2_2") (pintype "passive"))
      (node (ref "C36") (pin "2") (pinfunction "2_2") (pintype "passive"))
      (node (ref "C39") (pin "2") (pinfunction "2_2") (pintype "passive"))
      (node (ref "D14") (pin "2") (pinfunction "2_2") (pintype "passive"))
      (node (ref "FB4") (pin "1") (pinfunction "1_1") (pintype "passive"))
      (node (ref "FB5") (pin "1") (pinfunction "1_1") (pintype "passive"))
      (node (ref "R28") (pin "1") (pinfunction "1_1") (pintype "passive"))
      (node (ref "R29") (pin "1") (pinfunction "1_1") (pintype "passive"))
      (node (ref "R30") (pin "1") (pinfunction "1_1") (pintype "passive"))
      (node (ref "R31") (pin "1") (pinfunction "1_1") (pintype "passive"))
      (node (ref "R32") (pin "1") (pinfunction "1_1") (pintype "passive"))
      (node (ref "R35") (pin "2") (pinfunction "2_2") (pintype "passive"))
      (node (ref "R40") (pin "2") (pinfunction "2_2") (pintype "passive"))
      (node (ref "R42") (pin "1") (pinfunction "1_1") (pintype "passive"))
      (node (ref "R48") (pin "1") (pinfunction "1_1") (pintype "passive"))
      (node (ref "R50") (pin "1") (pinfunction "1_1") (pintype "passive"))
      (node (ref "R51") (pin "1") (pinfunction "1_1") (pintype "passive"))
      (node (ref "R52") (pin "1") (pinfunction "1_1") (pintype "passive"))
      (node (ref "R54") (pin "2") (pinfunction "2_2") (pintype "passive"))
      (node (ref "R57") (pin "2") (pinfunction "2_2") (pintype "passive"))
      (node (ref "U6") (pin "20") (pinfunction "VCCIO_20") (pintype "power_in"))
      (node (ref "U6") (pin "31") (pinfunction "VCCIO_31") (pintype "power_in"))
      (node (ref "U6") (pin "42") (pinfunction "VCCIO_42") (pintype "power_in"))
      (node (ref "U6") (pin "50") (pinfunction "VREGIN_50") (pintype "power_in"))
      (node (ref "U6") (pin "56") (pinfunction "VCCIO_56") (pintype "power_in"))
      (node (ref "U7") (pin "10") (pinfunction "VCC_10") (pintype "passive"))
      (node (ref "U8") (pin "5") (pinfunction "VCC_5") (pintype "passive"))
      (node (ref "U9") (pin "8") (pinfunction "VCC_8") (pintype "passive"))
      (node (ref "X1") (pin "1") (pinfunction "~{ST}_1") (pintype "passive"))
      (node (ref "X1") (pin "4") (pinfunction "VCC_4") (pintype "passive"))
    )
    (net (code "50") (name "unconnected-(J6-Pad12)") (class "Default")
      (node (ref "J6") (pin "12") (pinfunction "12_12") (pintype "passive+no_connect"))
    )
    (net (code "51") (name "unconnected-(J8-SBU1-PadA8)") (class "Default")
      (node (ref "J8") (pin "A8") (pinfunction "SBU1_A8") (pintype "bidirectional+no_connect"))
    )
    (net (code "52") (name "unconnected-(J8-SBU2-PadB8)") (class "Default")
      (node (ref "J8") (pin "B8") (pinfunction "SBU2_B8") (pintype "bidirectional+no_connect"))
    )
    (net (code "53") (name "unconnected-(U6-ACBUS0-Pad26)") (class "Default")
      (node (ref "U6") (pin "26") (pinfunction "ACBUS0_26") (pintype "bidirectional+no_connect"))
    )
    (net (code "54") (name "unconnected-(U6-ACBUS1-Pad27)") (class "Default")
      (node (ref "U6") (pin "27") (pinfunction "ACBUS1_27") (pintype "bidirectional+no_connect"))
    )
    (net (code "55") (name "unconnected-(U6-ACBUS2-Pad28)") (class "Default")
      (node (ref "U6") (pin "28") (pinfunction "ACBUS2_28") (pintype "bidirectional+no_connect"))
    )
    (net (code "56") (name "unconnected-(U6-ACBUS3-Pad29)") (class "Default")
      (node (ref "U6") (pin "29") (pinfunction "ACBUS3_29") (pintype "bidirectional+no_connect"))
    )
    (net (code "57") (name "unconnected-(U6-ACBUS4-Pad30)") (class "Default")
      (node (ref "U6") (pin "30") (pinfunction "ACBUS4_30") (pintype "bidirectional+no_connect"))
    )
    (net (code "58") (name "unconnected-(U6-ACBUS5-Pad32)") (class "Default")
      (node (ref "U6") (pin "32") (pinfunction "ACBUS5_32") (pintype "bidirectional+no_connect"))
    )
    (net (code "59") (name "unconnected-(U6-ACBUS6-Pad33)") (class "Default")
      (node (ref "U6") (pin "33") (pinfunction "ACBUS6_33") (pintype "bidirectional+no_connect"))
    )
    (net (code "60") (name "unconnected-(U6-ACBUS7-Pad34)") (class "Default")
      (node (ref "U6") (pin "34") (pinfunction "ACBUS7_34") (pintype "bidirectional+no_connect"))
    )
    (net (code "61") (name "unconnected-(U6-ADBUS5-Pad22)") (class "Default")
      (node (ref "U6") (pin "22") (pinfunction "ADBUS5_22") (pintype "bidirectional+no_connect"))
    )
    (net (code "62") (name "unconnected-(U6-ADBUS7-Pad24)") (class "Default")
      (node (ref "U6") (pin "24") (pinfunction "ADBUS7_24") (pintype "bidirectional+no_connect"))
    )
    (net (code "63") (name "unconnected-(U6-BCBUS0-Pad48)") (class "Default")
      (node (ref "U6") (pin "48") (pinfunction "BCBUS0_48") (pintype "bidirectional+no_connect"))
    )
    (net (code "64") (name "unconnected-(U6-BCBUS1-Pad52)") (class "Default")
      (node (ref "U6") (pin "52") (pinfunction "BCBUS1_52") (pintype "bidirectional+no_connect"))
    )
    (net (code "65") (name "unconnected-(U6-BCBUS2-Pad53)") (class "Default")
      (node (ref "U6") (pin "53") (pinfunction "BCBUS2_53") (pintype "bidirectional+no_connect"))
    )
    (net (code "66") (name "unconnected-(U6-BCBUS5-Pad57)") (class "Default")
      (node (ref "U6") (pin "57") (pinfunction "BCBUS5_57") (pintype "bidirectional+no_connect"))
    )
    (net (code "67") (name "unconnected-(U6-BCBUS6-Pad58)") (class "Default")
      (node (ref "U6") (pin "58") (pinfunction "BCBUS6_58") (pintype "bidirectional+no_connect"))
    )
    (net (code "68") (name "unconnected-(U6-BDBUS2-Pad40)") (class "Default")
      (node (ref "U6") (pin "40") (pinfunction "BDBUS2_40") (pintype "bidirectional+no_connect"))
    )
    (net (code "69") (name "unconnected-(U6-BDBUS3-Pad41)") (class "Default")
      (node (ref "U6") (pin "41") (pinfunction "BDBUS3_41") (pintype "bidirectional+no_connect"))
    )
    (net (code "70") (name "unconnected-(U6-BDBUS4-Pad43)") (class "Default")
      (node (ref "U6") (pin "43") (pinfunction "BDBUS4_43") (pintype "bidirectional+no_connect"))
    )
    (net (code "71") (name "unconnected-(U6-BDBUS5-Pad44)") (class "Default")
      (node (ref "U6") (pin "44") (pinfunction "BDBUS5_44") (pintype "bidirectional+no_connect"))
    )
    (net (code "72") (name "unconnected-(U6-BDBUS6-Pad45)") (class "Default")
      (node (ref "U6") (pin "45") (pinfunction "BDBUS6_45") (pintype "bidirectional+no_connect"))
    )
    (net (code "73") (name "unconnected-(U6-BDBUS7-Pad46)") (class "Default")
      (node (ref "U6") (pin "46") (pinfunction "BDBUS7_46") (pintype "bidirectional+no_connect"))
    )
    (net (code "74") (name "unconnected-(U6-OSCO-Pad3)") (class "Default")
      (node (ref "U6") (pin "3") (pinfunction "OSCO_3") (pintype "output+no_connect"))
    )
    (net (code "75") (name "unconnected-(U6-~{PWREN}-Pad60)") (class "Default")
      (node (ref "U6") (pin "60") (pinfunction "~{PWREN}_60") (pintype "output+no_connect"))
    )
    (net (code "76") (name "unconnected-(U6-~{SUSPEND}-Pad36)") (class "Default")
      (node (ref "U6") (pin "36") (pinfunction "~{SUSPEND}_36") (pintype "output+no_connect"))
    )
    (net (code "77") (name "unconnected-(U9-NC-Pad7)") (class "Default")
      (node (ref "U9") (pin "7") (pinfunction "NC_7") (pintype "passive+no_connect"))
    )
    (net (code "78") (name "unconnected-(U9-ORG-Pad6)") (class "Default")
      (node (ref "U9") (pin "6") (pinfunction "ORG_6") (pintype "passive+no_connect"))
    )
  )
)
